# ife19_TS_TSAL-Discharge-TSMP.net
KiCad netlist of a schematic drawn in Altium Designer
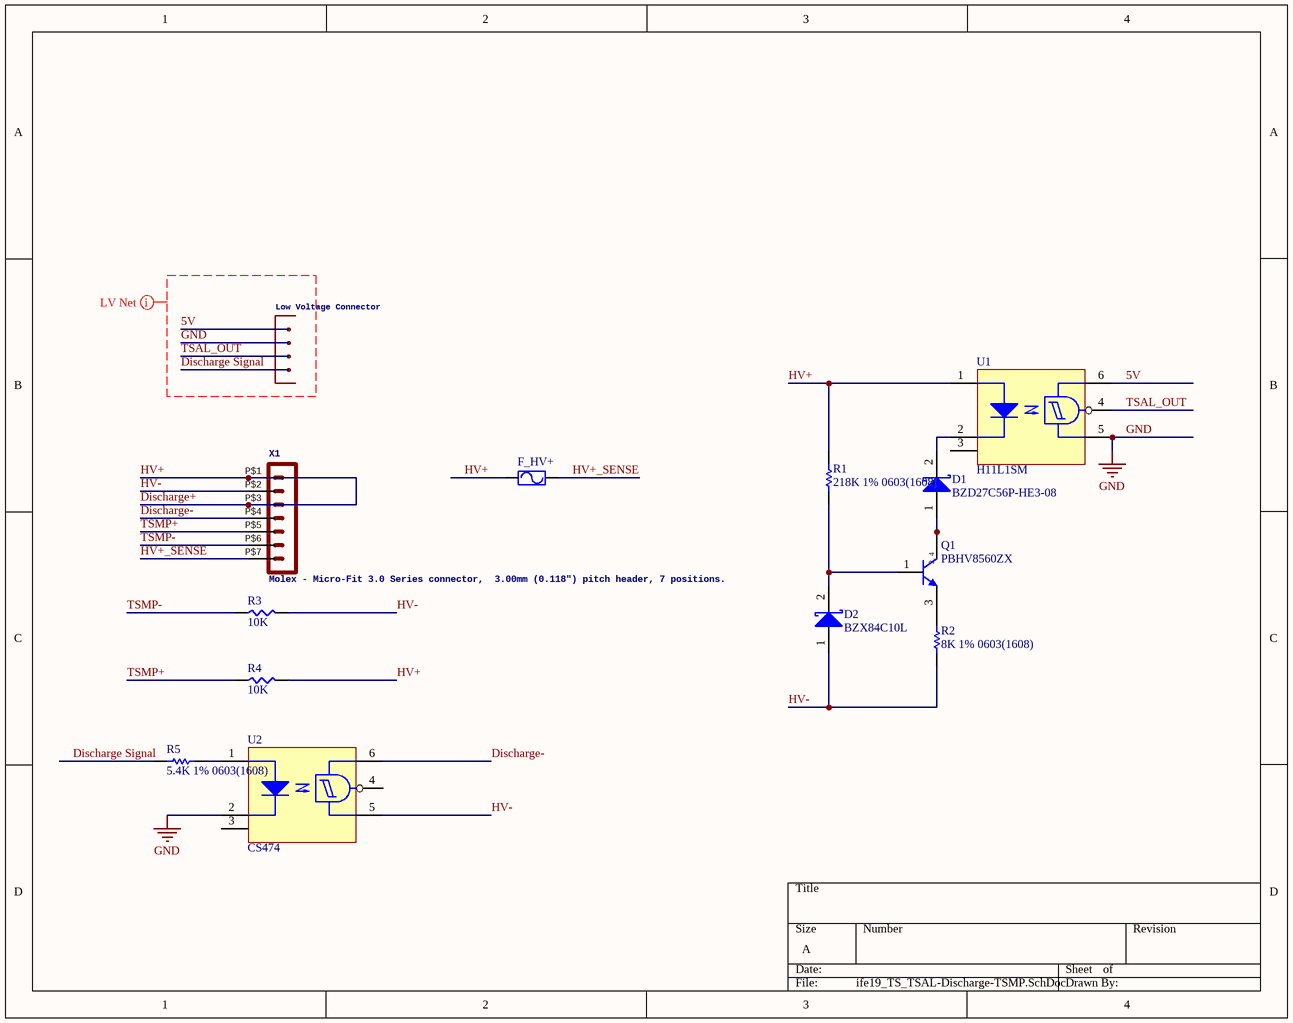
[diagram p0: ife19_TS_TSAL-Discharge-TSMP.SchDoc]

(export (version "E")
  (design (tool "Eeschema 10.0.6"))
  (components
    (comp (ref "D1")
      (value "BZD27C56P-HE3-08")
      (footprint "VISH-DO-219AB_V")
      (description "Schottky Rectifier, 30 V, 1.1 A, 2-Pin DO-219AB (SMF), RoHS, Tape and Reel")
      (fields (field (name "PARTNUMBER") "SL03-GS08CT") (field (name "MANUFACTURER") "Vishay Semiconductor"))
      (libsource (lib "Altium Content Vault") (part "DSKY-AK-2"))
    )
    (comp (ref "D2")
      (value "BZX84C10L")
      (footprint "VISH-DO-219AB_V")
      (description "Schottky Rectifier, 30 V, 1.1 A, 2-Pin DO-219AB (SMF), RoHS, Tape and Reel")
      (fields (field (name "PARTNUMBER") "SL03-GS08CT") (field (name "MANUFACTURER") "Vishay Semiconductor"))
      (libsource (lib "Altium Content Vault") (part "DSKY-AK-2"))
    )
    (comp (ref "F_HV+")
      (value "FUSE_885")
      (footprint "FUSE_885")
      (libsource (lib "altium-import") (part "root_0_FUSE_885_"))
    )
    (comp (ref "Low Voltage Connector")
      (value "~")
      (footprint "505575-04")
      (fields (field (name "LIBRARYNAME") "MOLEX Micro-Lock"))
      (libsource (lib "MOLEX Micro-Lock (2)") (part "505575-04"))
    )
    (comp (ref "Q1")
      (value "PBHV8560ZX")
      (footprint "NXP-SOT223_L")
      (description "NPN Medium Power Transistor, 60 V, 1 A, -55 to 150 degC, 4-Pin SOT223, RoHS, Tape and Reel")
      (fields (field (name "MANUFACTURER") "NXP Semiconductors"))
      (libsource (lib "Altium Content Vault") (part "BJT-NPN-BCEC-4"))
    )
    (comp (ref "R1")
      (value "218K 1% 0603(1608)")
      (footprint "RESC0603(1608)_L")
      (description "249K 0.1W 1% 0603 (1608 Metric)  SMD")
      (fields (field (name "POWER") "0.1 W") (field (name "TOLERANCE") "1 %"))
      (libsource (lib "Altium Content Vault") (part "RES"))
    )
    (comp (ref "R2")
      (value "8K 1% 0603(1608)")
      (footprint "RESC0603(1608)_L")
      (description "348K 0.1W 1% 0603 (1608 Metric)  SMD")
      (fields (field (name "TOLERANCE") "1 %") (field (name "POWER") "0.1 W"))
      (libsource (lib "Altium Content Vault") (part "RES"))
    )
    (comp (ref "R3")
      (value "10K")
      (footprint "Ohmite 45")
      (libsource (lib "IFE_Resistors (2)") (part "Ohmite 40 Series"))
    )
    (comp (ref "R4")
      (value "10K")
      (footprint "Ohmite 45")
      (libsource (lib "IFE_Resistors (2)") (part "Ohmite 40 Series"))
    )
    (comp (ref "R5")
      (value "5.4K 1% 0603(1608)")
      (footprint "RESC0603(1608)_L")
      (description "249K 0.1W 1% 0603 (1608 Metric)  SMD")
      (fields (field (name "POWER") "0.1 W") (field (name "TOLERANCE") "1 %"))
      (libsource (lib "Altium Content Vault") (part "RES"))
    )
    (comp (ref "U1")
      (value "H11L1SM")
      (footprint "FAIR-SMT-6_V")
      (description "Schmitt Trigger Output Optocoupler, 3 to 15 V, -40 to 85 degC, 6-Pin SMT, RoHS, Tube")
      (fields (field (name "MANUFACTURER") "Fairchild Semiconductor"))
      (libsource (lib "Altium Content Vault") (part "FAIR-H11L1M-6"))
    )
    (comp (ref "U2")
      (value "CS474")
      (footprint "FAIR-SMT-6_V")
      (description "Schmitt Trigger Output Optocoupler, 3 to 15 V, -40 to 85 degC, 6-Pin SMT, RoHS, Tube")
      (fields (field (name "MANUFACTURER") "Fairchild Semiconductor"))
      (libsource (lib "Altium Content Vault") (part "FAIR-H11L1M-6"))
    )
    (comp (ref "X1")
      (value "Molex - Micro-Fit 3.0 Series connector,  3.00mm (0.118\") pitch header, 7 positions.")
      (footprint "43650-0724")
      (libsource (lib "altium-import") (part "root_0_POS7_MF43650-0724_"))
    )
  )
  (nets
    (net (code "1") (name "/5V") (class "Default")
      (node (ref "Low Voltage Connector") (pin "1") (pinfunction "1_1") (pintype "passive"))
      (node (ref "U1") (pin "6") (pinfunction "VCC_6") (pintype "power_in"))
    )
    (net (code "2") (name "/Discharge Signal") (class "Default")
      (node (ref "Low Voltage Connector") (pin "4") (pinfunction "4_4") (pintype "passive"))
      (node (ref "R5") (pin "2") (pinfunction "2_2") (pintype "passive"))
    )
    (net (code "3") (name "/Discharge+") (class "Default")
      (node (ref "F_HV+") (pin "2") (pinfunction "2_2") (pintype "passive"))
      (node (ref "R1") (pin "2") (pinfunction "2_2") (pintype "passive"))
      (node (ref "R4") (pin "2") (pinfunction "2_2") (pintype "passive"))
      (node (ref "U1") (pin "1") (pinfunction "ANODE_1") (pintype "passive"))
      (node (ref "X1") (pin "P$1") (pinfunction "1_P$1") (pintype "passive"))
      (node (ref "X1") (pin "P$3") (pinfunction "3_P$3") (pintype "passive"))
    )
    (net (code "4") (name "/Discharge-") (class "Default")
      (node (ref "U2") (pin "6") (pinfunction "VCC_6") (pintype "power_in"))
      (node (ref "X1") (pin "P$4") (pinfunction "4_P$4") (pintype "passive"))
    )
    (net (code "5") (name "/HV+_SENSE") (class "Default")
      (node (ref "F_HV+") (pin "1") (pinfunction "1_1") (pintype "passive"))
      (node (ref "X1") (pin "P$7") (pinfunction "7_P$7") (pintype "passive"))
    )
    (net (code "6") (name "/HV-") (class "Default")
      (node (ref "D2") (pin "1") (pinfunction "A_1") (pintype "passive"))
      (node (ref "R2") (pin "1") (pinfunction "1_1") (pintype "passive"))
      (node (ref "R3") (pin "2") (pinfunction "2_2") (pintype "passive"))
      (node (ref "U2") (pin "5") (pinfunction "GND_5") (pintype "power_in"))
      (node (ref "X1") (pin "P$2") (pinfunction "2_P$2") (pintype "passive"))
    )
    (net (code "7") (name "/TSAL_OUT") (class "Default")
      (node (ref "Low Voltage Connector") (pin "3") (pinfunction "3_3") (pintype "passive"))
      (node (ref "U1") (pin "4") (pinfunction "VO_4") (pintype "open_collector"))
    )
    (net (code "8") (name "/TSMP+") (class "Default")
      (node (ref "R4") (pin "1") (pinfunction "1_1") (pintype "passive"))
      (node (ref "X1") (pin "P$5") (pinfunction "5_P$5") (pintype "passive"))
    )
    (net (code "9") (name "/TSMP-") (class "Default")
      (node (ref "R3") (pin "1") (pinfunction "1_1") (pintype "passive"))
      (node (ref "X1") (pin "P$6") (pinfunction "6_P$6") (pintype "passive"))
    )
    (net (code "10") (name "GND") (class "Default")
      (node (ref "Low Voltage Connector") (pin "2") (pinfunction "2_2") (pintype "passive"))
      (node (ref "U1") (pin "5") (pinfunction "GND_5") (pintype "power_in"))
      (node (ref "U2") (pin "2") (pinfunction "CATHODE_2") (pintype "passive"))
    )
    (net (code "11") (name "Net-(D1-A)") (class "Default")
      (node (ref "D1") (pin "1") (pinfunction "A_1") (pintype "passive"))
      (node (ref "Q1") (pin "2") (pinfunction "C_2") (pintype "passive"))
      (node (ref "Q1") (pin "4") (pinfunction "C_4") (pintype "passive"))
    )
    (net (code "12") (name "Net-(D1-K)") (class "Default")
      (node (ref "D1") (pin "2") (pinfunction "K_2") (pintype "passive"))
      (node (ref "U1") (pin "2") (pinfunction "CATHODE_2") (pintype "passive"))
    )
    (net (code "13") (name "Net-(D2-K)") (class "Default")
      (node (ref "D2") (pin "2") (pinfunction "K_2") (pintype "passive"))
      (node (ref "Q1") (pin "1") (pinfunction "B_1") (pintype "passive"))
      (node (ref "R1") (pin "1") (pinfunction "1_1") (pintype "passive"))
    )
    (net (code "14") (name "Net-(Q1-E)") (class "Default")
      (node (ref "Q1") (pin "3") (pinfunction "E_3") (pintype "passive"))
      (node (ref "R2") (pin "2") (pinfunction "2_2") (pintype "passive"))
    )
    (net (code "15") (name "Net-(U2-ANODE)") (class "Default")
      (node (ref "R5") (pin "1") (pinfunction "1_1") (pintype "passive"))
      (node (ref "U2") (pin "1") (pinfunction "ANODE_1") (pintype "passive"))
    )
    (net (code "16") (name "unconnected-(U1-NC-Pad3)") (class "Default")
      (node (ref "U1") (pin "3") (pinfunction "NC_3") (pintype "passive"))
    )
    (net (code "17") (name "unconnected-(U2-NC-Pad3)") (class "Default")
      (node (ref "U2") (pin "3") (pinfunction "NC_3") (pintype "passive"))
    )
    (net (code "18") (name "unconnected-(U2-VO-Pad4)") (class "Default")
      (node (ref "U2") (pin "4") (pinfunction "VO_4") (pintype "open_collector"))
    )
  )
)
